# HeadphoneSlice.net
KiCad netlist of a schematic drawn in EAGLE
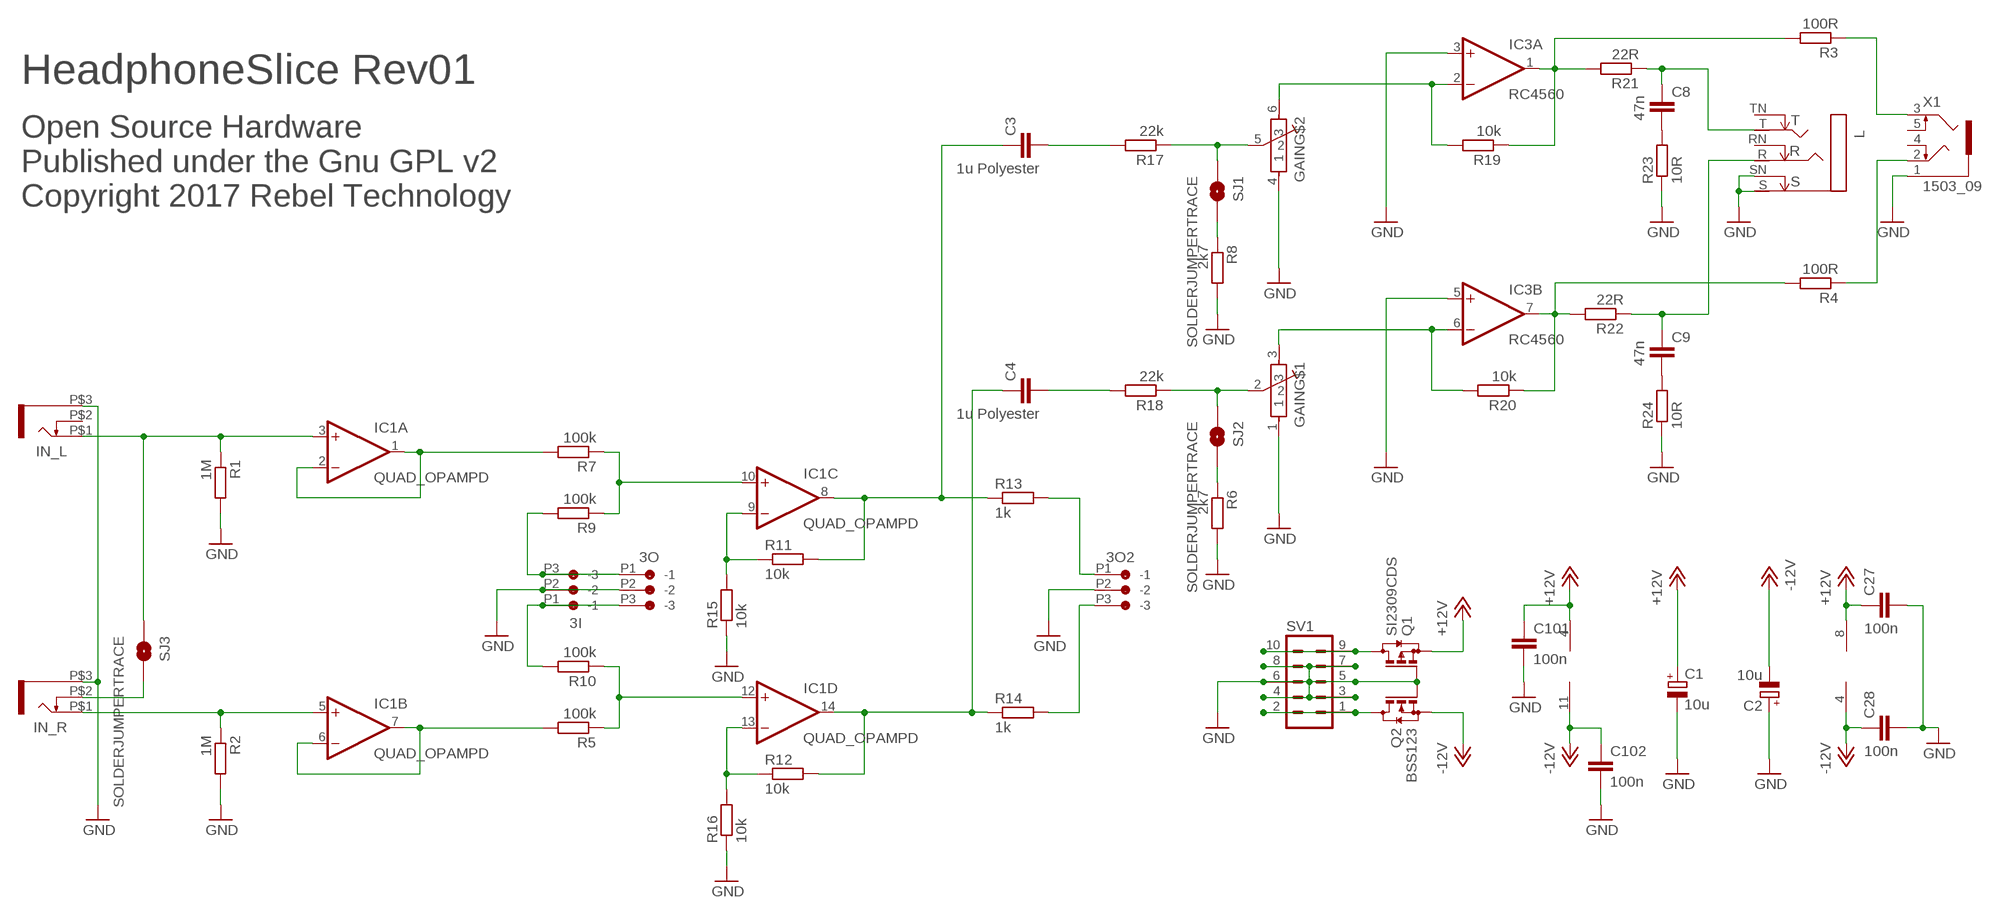
[diagram p0: schematic, sheet 1]

(export (version "E")
  (design (tool "Eeschema 10.0.6"))
  (components
    (comp (ref "3I")
      (value "CON-JST_PH_3W")
      (footprint "eagle-import:CON-JST_PH_3W")
      (libsource (lib "eagle-import") (part "CON-JST_PH_3W"))
    )
    (comp (ref "3O")
      (value "CON-JST_PH_3W")
      (footprint "eagle-import:CON-JST_PH_3W")
      (libsource (lib "eagle-import") (part "CON-JST_PH_3W"))
    )
    (comp (ref "3O2")
      (value "CON-JST_PH_3W")
      (footprint "eagle-import:CON-JST_PH_3W")
      (libsource (lib "eagle-import") (part "CON-JST_PH_3W"))
    )
    (comp (ref "C1")
      (value "10u")
      (footprint "eagle-import:153CLV-0505")
      (libsource (lib "eagle-import") (part "CPOL-EU153CLV-0505"))
    )
    (comp (ref "C2")
      (value "10u")
      (footprint "eagle-import:153CLV-0505")
      (libsource (lib "eagle-import") (part "CPOL-EU153CLV-0505"))
    )
    (comp (ref "C3")
      (value "1u Polyester")
      (footprint "eagle-import:C1210")
      (libsource (lib "eagle-import") (part "C-EUC1210"))
    )
    (comp (ref "C4")
      (value "1u Polyester")
      (footprint "eagle-import:C1210")
      (libsource (lib "eagle-import") (part "C-EUC1210"))
    )
    (comp (ref "C8")
      (value "47n")
      (footprint "eagle-import:C0603")
      (libsource (lib "eagle-import") (part "C-EUC0603"))
    )
    (comp (ref "C9")
      (value "47n")
      (footprint "eagle-import:C0603")
      (libsource (lib "eagle-import") (part "C-EUC0603"))
    )
    (comp (ref "C27")
      (value "100n")
      (footprint "eagle-import:C0603")
      (libsource (lib "eagle-import") (part "C-EUC0603"))
    )
    (comp (ref "C28")
      (value "100n")
      (footprint "eagle-import:C0603")
      (libsource (lib "eagle-import") (part "C-EUC0603"))
    )
    (comp (ref "C101")
      (value "100n")
      (footprint "eagle-import:C0603")
      (libsource (lib "eagle-import") (part "C-EUC0603"))
    )
    (comp (ref "C102")
      (value "100n")
      (footprint "eagle-import:C0603")
      (libsource (lib "eagle-import") (part "C-EUC0603"))
    )
    (comp (ref "GAIN")
      (value "POT-BOURNS-PTD902")
      (footprint "eagle-import:POT-BOURNS-PTD902")
      (libsource (lib "eagle-import") (part "POT-BOURNS-PTD902"))
    )
    (comp (ref "IC1")
      (value "QUAD_OPAMPD")
      (footprint "eagle-import:SO14")
      (libsource (lib "eagle-import") (part "QUAD_OPAMPD"))
    )
    (comp (ref "IC3")
      (value "RC4560")
      (footprint "eagle-import:SO08")
      (libsource (lib "eagle-import") (part "NE5532D"))
    )
    (comp (ref "IN_L")
      (value "JACK-UJ-3502-RSLOT")
      (footprint "eagle-import:UJ-3502-R-SLOT")
      (libsource (lib "eagle-import") (part "JACK-UJ-3502-RSLOT"))
    )
    (comp (ref "IN_R")
      (value "JACK-UJ-3502-RSLOT")
      (footprint "eagle-import:UJ-3502-R-SLOT")
      (libsource (lib "eagle-import") (part "JACK-UJ-3502-RSLOT"))
    )
    (comp (ref "L")
      (value "NEUTRIK_NMJ6HCD2")
      (footprint "eagle-import:NMJ6HCD2")
      (libsource (lib "eagle-import") (part "NEUTRIK_NMJ6HCD2"))
    )
    (comp (ref "Q1")
      (value "SI2309CDS")
      (footprint "eagle-import:SOT23")
      (libsource (lib "eagle-import") (part "BSS84"))
    )
    (comp (ref "Q2")
      (value "BSS123")
      (footprint "eagle-import:SOT23")
      (libsource (lib "eagle-import") (part "BSS123"))
    )
    (comp (ref "R1")
      (value "1M")
      (footprint "eagle-import:0603")
      (libsource (lib "eagle-import") (part "R-EU_0603"))
    )
    (comp (ref "R2")
      (value "1M")
      (footprint "eagle-import:0603")
      (libsource (lib "eagle-import") (part "R-EU_0603"))
    )
    (comp (ref "R3")
      (value "100R")
      (footprint "eagle-import:0603")
      (libsource (lib "eagle-import") (part "R-EU_0603"))
    )
    (comp (ref "R4")
      (value "100R")
      (footprint "eagle-import:0603")
      (libsource (lib "eagle-import") (part "R-EU_0603"))
    )
    (comp (ref "R5")
      (value "100k")
      (footprint "eagle-import:0603")
      (libsource (lib "eagle-import") (part "R-EU_0603"))
    )
    (comp (ref "R6")
      (value "2k7")
      (footprint "eagle-import:0603")
      (libsource (lib "eagle-import") (part "R-EU_0603"))
    )
    (comp (ref "R7")
      (value "100k")
      (footprint "eagle-import:0603")
      (libsource (lib "eagle-import") (part "R-EU_0603"))
    )
    (comp (ref "R8")
      (value "2k7")
      (footprint "eagle-import:0603")
      (libsource (lib "eagle-import") (part "R-EU_0603"))
    )
    (comp (ref "R9")
      (value "100k")
      (footprint "eagle-import:0603")
      (libsource (lib "eagle-import") (part "R-EU_0603"))
    )
    (comp (ref "R10")
      (value "100k")
      (footprint "eagle-import:0603")
      (libsource (lib "eagle-import") (part "R-EU_0603"))
    )
    (comp (ref "R11")
      (value "10k")
      (footprint "eagle-import:0603")
      (libsource (lib "eagle-import") (part "R-EU_0603"))
    )
    (comp (ref "R12")
      (value "10k")
      (footprint "eagle-import:0603")
      (libsource (lib "eagle-import") (part "R-EU_0603"))
    )
    (comp (ref "R13")
      (value "1k")
      (footprint "eagle-import:0603")
      (libsource (lib "eagle-import") (part "R-EU_0603"))
    )
    (comp (ref "R14")
      (value "1k")
      (footprint "eagle-import:0603")
      (libsource (lib "eagle-import") (part "R-EU_0603"))
    )
    (comp (ref "R15")
      (value "10k")
      (footprint "eagle-import:0603")
      (libsource (lib "eagle-import") (part "R-EU_0603"))
    )
    (comp (ref "R16")
      (value "10k")
      (footprint "eagle-import:0603")
      (libsource (lib "eagle-import") (part "R-EU_0603"))
    )
    (comp (ref "R17")
      (value "22k")
      (footprint "eagle-import:0603")
      (libsource (lib "eagle-import") (part "R-EU_0603"))
    )
    (comp (ref "R18")
      (value "22k")
      (footprint "eagle-import:0603")
      (libsource (lib "eagle-import") (part "R-EU_0603"))
    )
    (comp (ref "R19")
      (value "10k")
      (footprint "eagle-import:0603")
      (libsource (lib "eagle-import") (part "R-EU_0603"))
    )
    (comp (ref "R20")
      (value "10k")
      (footprint "eagle-import:0603")
      (libsource (lib "eagle-import") (part "R-EU_0603"))
    )
    (comp (ref "R21")
      (value "22R")
      (footprint "eagle-import:0603")
      (libsource (lib "eagle-import") (part "R-EU_0603"))
    )
    (comp (ref "R22")
      (value "22R")
      (footprint "eagle-import:0603")
      (libsource (lib "eagle-import") (part "R-EU_0603"))
    )
    (comp (ref "R23")
      (value "10R")
      (footprint "eagle-import:0603")
      (libsource (lib "eagle-import") (part "R-EU_0603"))
    )
    (comp (ref "R24")
      (value "10R")
      (footprint "eagle-import:0603")
      (libsource (lib "eagle-import") (part "R-EU_0603"))
    )
    (comp (ref "SJ1")
      (value "SOLDERJUMPERTRACE")
      (footprint "eagle-import:SJ_2S-TRACE")
      (libsource (lib "eagle-import") (part "SOLDERJUMPERTRACE"))
    )
    (comp (ref "SJ2")
      (value "SOLDERJUMPERTRACE")
      (footprint "eagle-import:SJ_2S-TRACE")
      (libsource (lib "eagle-import") (part "SOLDERJUMPERTRACE"))
    )
    (comp (ref "SJ3")
      (value "SOLDERJUMPERTRACE")
      (footprint "eagle-import:SJ_2S-TRACE")
      (libsource (lib "eagle-import") (part "SOLDERJUMPERTRACE"))
    )
    (comp (ref "SV1")
      (value "MA05-2")
      (footprint "eagle-import:MA05-2")
      (libsource (lib "eagle-import") (part "MA05-2"))
    )
    (comp (ref "X1")
      (value "1503_09")
      (footprint "eagle-import:1503_09")
      (libsource (lib "eagle-import") (part "1503_09"))
    )
  )
  (nets
    (net (code "1") (name "+12V") (class "Default")
      (node (ref "C1") (pin "+") (pinfunction "+_+") (pintype "passive"))
      (node (ref "C101") (pin "1") (pinfunction "1_1") (pintype "passive"))
      (node (ref "C27") (pin "1") (pinfunction "1_1") (pintype "passive"))
      (node (ref "IC1") (pin "4") (pinfunction "V+_4") (pintype "power_in"))
      (node (ref "IC3") (pin "8") (pinfunction "V+_8") (pintype "power_in"))
      (node (ref "Q1") (pin "2") (pinfunction "S_2") (pintype "passive"))
    )
    (net (code "2") (name "-12V") (class "Default")
      (node (ref "C102") (pin "1") (pinfunction "1_1") (pintype "passive"))
      (node (ref "C2") (pin "-") (pinfunction "-_-") (pintype "passive"))
      (node (ref "C28") (pin "1") (pinfunction "1_1") (pintype "passive"))
      (node (ref "IC1") (pin "11") (pinfunction "V-_11") (pintype "power_in"))
      (node (ref "IC3") (pin "4") (pinfunction "V-_4") (pintype "power_in"))
      (node (ref "Q2") (pin "2") (pinfunction "S_2") (pintype "passive"))
    )
    (net (code "3") (name "GND") (class "Default")
      (node (ref "3I") (pin "P2") (pinfunction "-2_P2") (pintype "bidirectional"))
      (node (ref "3O") (pin "P2") (pinfunction "-2_P2") (pintype "bidirectional"))
      (node (ref "3O2") (pin "P2") (pinfunction "-2_P2") (pintype "bidirectional"))
      (node (ref "C1") (pin "-") (pinfunction "-_-") (pintype "passive"))
      (node (ref "C101") (pin "2") (pinfunction "2_2") (pintype "passive"))
      (node (ref "C102") (pin "2") (pinfunction "2_2") (pintype "passive"))
      (node (ref "C2") (pin "+") (pinfunction "+_+") (pintype "passive"))
      (node (ref "C27") (pin "2") (pinfunction "2_2") (pintype "passive"))
      (node (ref "C28") (pin "2") (pinfunction "2_2") (pintype "passive"))
      (node (ref "GAIN") (pin "1") (pinfunction "1_1") (pintype "bidirectional"))
      (node (ref "GAIN") (pin "4") (pinfunction "1_4") (pintype "bidirectional"))
      (node (ref "IC3") (pin "3") (pinfunction "+IN_3") (pintype "input"))
      (node (ref "IC3") (pin "5") (pinfunction "+IN_5") (pintype "input"))
      (node (ref "IN_L") (pin "P$3") (pinfunction "SLEEVE_P$3") (pintype "passive"))
      (node (ref "IN_R") (pin "P$3") (pinfunction "SLEEVE_P$3") (pintype "passive"))
      (node (ref "L") (pin "S") (pinfunction "S_S") (pintype "passive"))
      (node (ref "L") (pin "SN") (pinfunction "SN_SN") (pintype "passive"))
      (node (ref "Q1") (pin "1") (pinfunction "G_1") (pintype "passive"))
      (node (ref "Q2") (pin "1") (pinfunction "G_1") (pintype "passive"))
      (node (ref "R1") (pin "2") (pinfunction "2_2") (pintype "passive"))
      (node (ref "R15") (pin "1") (pinfunction "1_1") (pintype "passive"))
      (node (ref "R16") (pin "1") (pinfunction "1_1") (pintype "passive"))
      (node (ref "R2") (pin "2") (pinfunction "2_2") (pintype "passive"))
      (node (ref "R23") (pin "1") (pinfunction "1_1") (pintype "passive"))
      (node (ref "R24") (pin "1") (pinfunction "1_1") (pintype "passive"))
      (node (ref "R6") (pin "2") (pinfunction "2_2") (pintype "passive"))
      (node (ref "R8") (pin "2") (pinfunction "2_2") (pintype "passive"))
      (node (ref "SV1") (pin "3") (pinfunction "3_3") (pintype "passive"))
      (node (ref "SV1") (pin "4") (pinfunction "4_4") (pintype "passive"))
      (node (ref "SV1") (pin "5") (pinfunction "5_5") (pintype "passive"))
      (node (ref "SV1") (pin "6") (pinfunction "6_6") (pintype "passive"))
      (node (ref "SV1") (pin "7") (pinfunction "7_7") (pintype "passive"))
      (node (ref "SV1") (pin "8") (pinfunction "8_8") (pintype "passive"))
      (node (ref "X1") (pin "1") (pinfunction "1_1") (pintype "passive"))
    )
    (net (code "4") (name "Net-(3I--1)") (class "Default")
      (node (ref "3I") (pin "P1") (pinfunction "-1_P1") (pintype "bidirectional"))
      (node (ref "3O") (pin "P3") (pinfunction "-3_P3") (pintype "bidirectional"))
      (node (ref "R10") (pin "2") (pinfunction "2_2") (pintype "passive"))
    )
    (net (code "5") (name "Net-(3I--3)") (class "Default")
      (node (ref "3I") (pin "P3") (pinfunction "-3_P3") (pintype "bidirectional"))
      (node (ref "3O") (pin "P1") (pinfunction "-1_P1") (pintype "bidirectional"))
      (node (ref "R9") (pin "2") (pinfunction "2_2") (pintype "passive"))
    )
    (net (code "6") (name "Net-(3O2--1)") (class "Default")
      (node (ref "3O2") (pin "P1") (pinfunction "-1_P1") (pintype "bidirectional"))
      (node (ref "R13") (pin "2") (pinfunction "2_2") (pintype "passive"))
    )
    (net (code "7") (name "Net-(3O2--3)") (class "Default")
      (node (ref "3O2") (pin "P3") (pinfunction "-3_P3") (pintype "bidirectional"))
      (node (ref "R14") (pin "2") (pinfunction "2_2") (pintype "passive"))
    )
    (net (code "8") (name "Net-(C3-Pad2)") (class "Default")
      (node (ref "C3") (pin "2") (pinfunction "2_2") (pintype "passive"))
      (node (ref "R17") (pin "2") (pinfunction "2_2") (pintype "passive"))
    )
    (net (code "9") (name "Net-(C4-Pad2)") (class "Default")
      (node (ref "C4") (pin "2") (pinfunction "2_2") (pintype "passive"))
      (node (ref "R18") (pin "2") (pinfunction "2_2") (pintype "passive"))
    )
    (net (code "10") (name "Net-(C8-Pad1)") (class "Default")
      (node (ref "C8") (pin "1") (pinfunction "1_1") (pintype "passive"))
      (node (ref "L") (pin "T") (pinfunction "T_T") (pintype "passive"))
      (node (ref "R21") (pin "1") (pinfunction "1_1") (pintype "passive"))
    )
    (net (code "11") (name "Net-(C8-Pad2)") (class "Default")
      (node (ref "C8") (pin "2") (pinfunction "2_2") (pintype "passive"))
      (node (ref "R23") (pin "2") (pinfunction "2_2") (pintype "passive"))
    )
    (net (code "12") (name "Net-(C9-Pad1)") (class "Default")
      (node (ref "C9") (pin "1") (pinfunction "1_1") (pintype "passive"))
      (node (ref "L") (pin "R") (pinfunction "R_R") (pintype "passive"))
      (node (ref "R22") (pin "1") (pinfunction "1_1") (pintype "passive"))
    )
    (net (code "13") (name "Net-(C9-Pad2)") (class "Default")
      (node (ref "C9") (pin "2") (pinfunction "2_2") (pintype "passive"))
      (node (ref "R24") (pin "2") (pinfunction "2_2") (pintype "passive"))
    )
    (net (code "14") (name "Net-(GAIN-Pad2)") (class "Default")
      (node (ref "GAIN") (pin "2") (pinfunction "2_2") (pintype "bidirectional"))
      (node (ref "R18") (pin "1") (pinfunction "1_1") (pintype "passive"))
      (node (ref "SJ2") (pin "1") (pinfunction "1_1") (pintype "passive"))
    )
    (net (code "15") (name "Net-(GAINB-2)") (class "Default")
      (node (ref "GAIN") (pin "5") (pinfunction "2_5") (pintype "bidirectional"))
      (node (ref "R17") (pin "1") (pinfunction "1_1") (pintype "passive"))
      (node (ref "SJ1") (pin "1") (pinfunction "1_1") (pintype "passive"))
    )
    (net (code "16") (name "Net-(GAINB-3)") (class "Default")
      (node (ref "GAIN") (pin "6") (pinfunction "3_6") (pintype "bidirectional"))
      (node (ref "IC3") (pin "2") (pinfunction "-IN_2") (pintype "input"))
      (node (ref "R19") (pin "2") (pinfunction "2_2") (pintype "passive"))
    )
    (net (code "17") (name "Net-(IC1A-+IN)") (class "Default")
      (node (ref "IC1") (pin "3") (pinfunction "+IN_3") (pintype "input"))
      (node (ref "IN_L") (pin "P$1") (pinfunction "TIP_P$1") (pintype "passive"))
      (node (ref "R1") (pin "1") (pinfunction "1_1") (pintype "passive"))
      (node (ref "SJ3") (pin "1") (pinfunction "1_1") (pintype "passive"))
    )
    (net (code "18") (name "Net-(IC1A--IN)") (class "Default")
      (node (ref "IC1") (pin "1") (pinfunction "OUT_1") (pintype "output"))
      (node (ref "IC1") (pin "2") (pinfunction "-IN_2") (pintype "input"))
      (node (ref "R7") (pin "2") (pinfunction "2_2") (pintype "passive"))
    )
    (net (code "19") (name "Net-(IC1B-+IN)") (class "Default")
      (node (ref "IC1") (pin "5") (pinfunction "+IN_5") (pintype "input"))
      (node (ref "IN_R") (pin "P$1") (pinfunction "TIP_P$1") (pintype "passive"))
      (node (ref "R2") (pin "1") (pinfunction "1_1") (pintype "passive"))
    )
    (net (code "20") (name "Net-(IC1B--IN)") (class "Default")
      (node (ref "IC1") (pin "6") (pinfunction "-IN_6") (pintype "input"))
      (node (ref "IC1") (pin "7") (pinfunction "OUT_7") (pintype "output"))
      (node (ref "R5") (pin "2") (pinfunction "2_2") (pintype "passive"))
    )
    (net (code "21") (name "Net-(IC1C-+IN)") (class "Default")
      (node (ref "IC1") (pin "10") (pinfunction "+IN_10") (pintype "input"))
      (node (ref "R7") (pin "1") (pinfunction "1_1") (pintype "passive"))
      (node (ref "R9") (pin "1") (pinfunction "1_1") (pintype "passive"))
    )
    (net (code "22") (name "Net-(IC1C--IN)") (class "Default")
      (node (ref "IC1") (pin "9") (pinfunction "-IN_9") (pintype "input"))
      (node (ref "R11") (pin "1") (pinfunction "1_1") (pintype "passive"))
      (node (ref "R15") (pin "2") (pinfunction "2_2") (pintype "passive"))
    )
    (net (code "23") (name "Net-(IC1C-OUT)") (class "Default")
      (node (ref "C3") (pin "1") (pinfunction "1_1") (pintype "passive"))
      (node (ref "IC1") (pin "8") (pinfunction "OUT_8") (pintype "output"))
      (node (ref "R11") (pin "2") (pinfunction "2_2") (pintype "passive"))
      (node (ref "R13") (pin "1") (pinfunction "1_1") (pintype "passive"))
    )
    (net (code "24") (name "Net-(IC1D-+IN)") (class "Default")
      (node (ref "IC1") (pin "12") (pinfunction "+IN_12") (pintype "input"))
      (node (ref "R10") (pin "1") (pinfunction "1_1") (pintype "passive"))
      (node (ref "R5") (pin "1") (pinfunction "1_1") (pintype "passive"))
    )
    (net (code "25") (name "Net-(IC1D--IN)") (class "Default")
      (node (ref "IC1") (pin "13") (pinfunction "-IN_13") (pintype "input"))
      (node (ref "R12") (pin "1") (pinfunction "1_1") (pintype "passive"))
      (node (ref "R16") (pin "2") (pinfunction "2_2") (pintype "passive"))
    )
    (net (code "26") (name "Net-(IC1D-OUT)") (class "Default")
      (node (ref "C4") (pin "1") (pinfunction "1_1") (pintype "passive"))
      (node (ref "IC1") (pin "14") (pinfunction "OUT_14") (pintype "output"))
      (node (ref "R12") (pin "2") (pinfunction "2_2") (pintype "passive"))
      (node (ref "R14") (pin "1") (pinfunction "1_1") (pintype "passive"))
    )
    (net (code "27") (name "Net-(IC3A-OUT)") (class "Default")
      (node (ref "IC3") (pin "1") (pinfunction "OUT_1") (pintype "output"))
      (node (ref "R19") (pin "1") (pinfunction "1_1") (pintype "passive"))
      (node (ref "R21") (pin "2") (pinfunction "2_2") (pintype "passive"))
      (node (ref "R3") (pin "2") (pinfunction "2_2") (pintype "passive"))
    )
    (net (code "28") (name "Net-(IC3B--IN)") (class "Default")
      (node (ref "GAIN") (pin "3") (pinfunction "3_3") (pintype "bidirectional"))
      (node (ref "IC3") (pin "6") (pinfunction "-IN_6") (pintype "input"))
      (node (ref "R20") (pin "2") (pinfunction "2_2") (pintype "passive"))
    )
    (net (code "29") (name "Net-(IC3B-OUT)") (class "Default")
      (node (ref "IC3") (pin "7") (pinfunction "OUT_7") (pintype "output"))
      (node (ref "R20") (pin "1") (pinfunction "1_1") (pintype "passive"))
      (node (ref "R22") (pin "2") (pinfunction "2_2") (pintype "passive"))
      (node (ref "R4") (pin "2") (pinfunction "2_2") (pintype "passive"))
    )
    (net (code "30") (name "Net-(IN_R-SW)") (class "Default")
      (node (ref "IN_R") (pin "P$2") (pinfunction "SW_P$2") (pintype "passive"))
      (node (ref "SJ3") (pin "2") (pinfunction "2_2") (pintype "passive"))
    )
    (net (code "31") (name "Net-(Q1-D)") (class "Default")
      (node (ref "Q1") (pin "3") (pinfunction "D_3") (pintype "passive"))
      (node (ref "SV1") (pin "10") (pinfunction "10_10") (pintype "passive"))
      (node (ref "SV1") (pin "9") (pinfunction "9_9") (pintype "passive"))
    )
    (net (code "32") (name "Net-(Q2-D)") (class "Default")
      (node (ref "Q2") (pin "3") (pinfunction "D_3") (pintype "passive"))
      (node (ref "SV1") (pin "1") (pinfunction "1_1") (pintype "passive"))
      (node (ref "SV1") (pin "2") (pinfunction "2_2") (pintype "passive"))
    )
    (net (code "33") (name "Net-(R3-Pad1)") (class "Default")
      (node (ref "R3") (pin "1") (pinfunction "1_1") (pintype "passive"))
      (node (ref "X1") (pin "3") (pinfunction "3_3") (pintype "passive"))
    )
    (net (code "34") (name "Net-(R4-Pad1)") (class "Default")
      (node (ref "R4") (pin "1") (pinfunction "1_1") (pintype "passive"))
      (node (ref "X1") (pin "2") (pinfunction "2_2") (pintype "passive"))
    )
    (net (code "35") (name "Net-(R6-Pad1)") (class "Default")
      (node (ref "R6") (pin "1") (pinfunction "1_1") (pintype "passive"))
      (node (ref "SJ2") (pin "2") (pinfunction "2_2") (pintype "passive"))
    )
    (net (code "36") (name "Net-(R8-Pad1)") (class "Default")
      (node (ref "R8") (pin "1") (pinfunction "1_1") (pintype "passive"))
      (node (ref "SJ1") (pin "2") (pinfunction "2_2") (pintype "passive"))
    )
    (net (code "37") (name "unconnected-(IN_L-SW-PadP$2)") (class "Default")
      (node (ref "IN_L") (pin "P$2") (pinfunction "SW_P$2") (pintype "passive"))
    )
    (net (code "38") (name "unconnected-(L-PadRN)") (class "Default")
      (node (ref "L") (pin "RN") (pinfunction "RN_RN") (pintype "passive"))
    )
    (net (code "39") (name "unconnected-(L-PadTN)") (class "Default")
      (node (ref "L") (pin "TN") (pinfunction "TN_TN") (pintype "passive"))
    )
    (net (code "40") (name "unconnected-(X1-Pad4)") (class "Default")
      (node (ref "X1") (pin "4") (pinfunction "4_4") (pintype "passive"))
    )
    (net (code "41") (name "unconnected-(X1-Pad5)") (class "Default")
      (node (ref "X1") (pin "5") (pinfunction "5_5") (pintype "passive"))
    )
  )
)
